# SPI_peripherals.net
KiCad netlist of a schematic drawn in Altium Designer
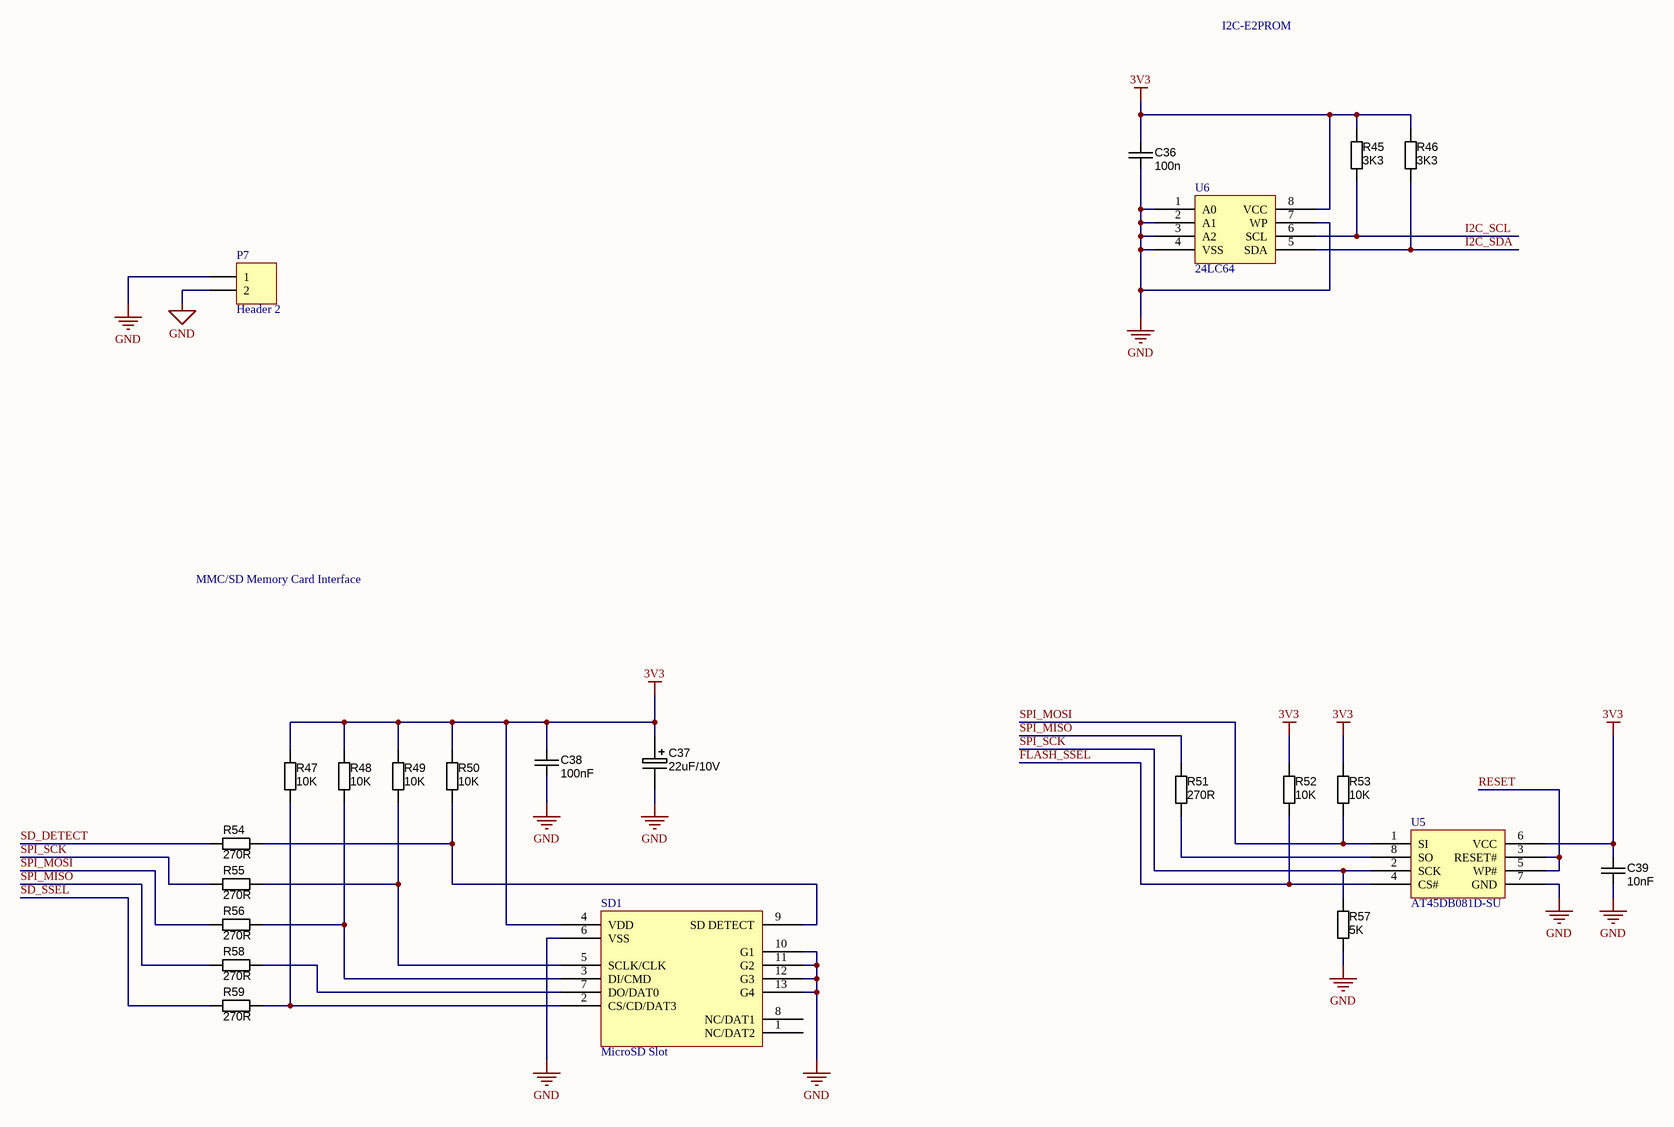
[diagram p0: SPI peripherals.SchDoc]

(export (version "E")
  (design (tool "Eeschema 10.0.6"))
  (components
    (comp (ref "C36")
      (value "100n")
      (footprint "CAPC1608N")
      (description "Capacitor SMD Cer 100nF 10% 50V X7R 0805")
      (fields (field (name "TOLERANCE") "?0%") (field (name "Comment") "approved sub OK"))
      (libsource (lib "PBL - Capacitors") (part "CAPC_100n_0805"))
    )
    (comp (ref "C37")
      (value "~")
      (footprint "CAPC3216N")
      (description "Capacitor SMD Tantalum 1uF 20% 10V 0805")
      (fields (field (name "TOLERANCE") "?0%") (field (name "RATINGS") "22uF/10V"))
      (libsource (lib "PBL - Capacitors") (part "CAPT_1u_0805_10V"))
    )
    (comp (ref "C38")
      (value "100nF")
      (footprint "CAPC1608N")
      (description "Capacitor SMD Cer 100nF 10% 50V X7R 0805")
      (fields (field (name "TOLERANCE") "?0%") (field (name "Comment") "approved sub OK"))
      (libsource (lib "PBL - Capacitors") (part "CAPC_100n_0805"))
    )
    (comp (ref "C39")
      (value "10nF")
      (footprint "CAPC1608N")
      (description "Capacitor SMD Cer 100nF 10% 50V X7R 0805")
      (fields (field (name "TOLERANCE") "?0%") (field (name "Comment") "approved sub OK"))
      (libsource (lib "PBL - Capacitors") (part "CAPC_100n_0805"))
    )
    (comp (ref "P7")
      (value "Header 2")
      (footprint "HDR1X2")
      (description "Header, 2-Pin")
      (fields (field (name "PUBLISHER") "Altium Limited"))
      (libsource (lib "Miscellaneous Connectors") (part "Header 2"))
    )
    (comp (ref "R45")
      (value "3K3")
      (footprint "RESC1005N")
      (description "Resistor SMD chip 330 Ohm 0.063W 5% 0402")
      (fields (field (name "TOLERANCE") "?%") (field (name "Comment") "Thick Film"))
      (libsource (lib "PBL - Resistors") (part "RES_330R_0402_5%"))
    )
    (comp (ref "R46")
      (value "3K3")
      (footprint "RESC1005N")
      (description "Resistor SMD chip 330 Ohm 0.063W 5% 0402")
      (fields (field (name "TOLERANCE") "?%") (field (name "Comment") "Thick Film"))
      (libsource (lib "PBL - Resistors") (part "RES_330R_0402_5%"))
    )
    (comp (ref "R47")
      (value "10K")
      (footprint "RESC1005N")
      (description "Resistor SMD chip 330 Ohm 0.063W 5% 0402")
      (fields (field (name "TOLERANCE") "?%") (field (name "Comment") "Thick Film"))
      (libsource (lib "") (part "RES_330R_0402_5%_2"))
    )
    (comp (ref "R48")
      (value "10K")
      (footprint "RESC1005N")
      (description "Resistor SMD chip 330 Ohm 0.063W 5% 0402")
      (fields (field (name "TOLERANCE") "?%") (field (name "Comment") "Thick Film"))
      (libsource (lib "") (part "RES_330R_0402_5%_2"))
    )
    (comp (ref "R49")
      (value "10K")
      (footprint "RESC1005N")
      (description "Resistor SMD chip 330 Ohm 0.063W 5% 0402")
      (fields (field (name "TOLERANCE") "?%") (field (name "Comment") "Thick Film"))
      (libsource (lib "") (part "RES_330R_0402_5%_2"))
    )
    (comp (ref "R50")
      (value "10K")
      (footprint "RESC1005N")
      (description "Resistor SMD chip 330 Ohm 0.063W 5% 0402")
      (fields (field (name "TOLERANCE") "?%") (field (name "Comment") "Thick Film"))
      (libsource (lib "") (part "RES_330R_0402_5%_2"))
    )
    (comp (ref "R51")
      (value "270R")
      (footprint "RESC1005N")
      (description "Resistor SMD chip 330 Ohm 0.063W 5% 0402")
      (fields (field (name "TOLERANCE") "?%") (field (name "Comment") "Thick Film"))
      (libsource (lib "PBL - Resistors") (part "RES_330R_0402_5%"))
    )
    (comp (ref "R52")
      (value "10K")
      (footprint "RESC1005N")
      (description "Resistor SMD chip 330 Ohm 0.063W 5% 0402")
      (fields (field (name "TOLERANCE") "?%") (field (name "Comment") "Thick Film"))
      (libsource (lib "PBL - Resistors") (part "RES_330R_0402_5%"))
    )
    (comp (ref "R53")
      (value "10K")
      (footprint "RESC1005N")
      (description "Resistor SMD chip 330 Ohm 0.063W 5% 0402")
      (fields (field (name "TOLERANCE") "?%") (field (name "Comment") "Thick Film"))
      (libsource (lib "PBL - Resistors") (part "RES_330R_0402_5%"))
    )
    (comp (ref "R54")
      (value "270R")
      (footprint "RESC1005N")
      (description "Resistor SMD chip 330 Ohm 0.063W 5% 0402")
      (fields (field (name "TOLERANCE") "?%") (field (name "Comment") "Thick Film"))
      (libsource (lib "") (part "RES_330R_0402_5%_1"))
    )
    (comp (ref "R55")
      (value "270R")
      (footprint "RESC1005N")
      (description "Resistor SMD chip 330 Ohm 0.063W 5% 0402")
      (fields (field (name "TOLERANCE") "?%") (field (name "Comment") "Thick Film"))
      (libsource (lib "") (part "RES_330R_0402_5%_1"))
    )
    (comp (ref "R56")
      (value "270R")
      (footprint "RESC1005N")
      (description "Resistor SMD chip 330 Ohm 0.063W 5% 0402")
      (fields (field (name "TOLERANCE") "?%") (field (name "Comment") "Thick Film"))
      (libsource (lib "") (part "RES_330R_0402_5%_1"))
    )
    (comp (ref "R57")
      (value "5K")
      (footprint "RESC1005N")
      (description "Resistor SMD chip 330 Ohm 0.063W 5% 0402")
      (fields (field (name "TOLERANCE") "?%") (field (name "Comment") "Thick Film"))
      (libsource (lib "PBL - Resistors") (part "RES_330R_0402_5%"))
    )
    (comp (ref "R58")
      (value "270R")
      (footprint "RESC1005N")
      (description "Resistor SMD chip 330 Ohm 0.063W 5% 0402")
      (fields (field (name "TOLERANCE") "?%") (field (name "Comment") "Thick Film"))
      (libsource (lib "") (part "RES_330R_0402_5%_1"))
    )
    (comp (ref "R59")
      (value "270R")
      (footprint "RESC1005N")
      (description "Resistor SMD chip 330 Ohm 0.063W 5% 0402")
      (fields (field (name "TOLERANCE") "?%") (field (name "Comment") "Thick Film"))
      (libsource (lib "") (part "RES_330R_0402_5%_1"))
    )
    (comp (ref "SD1")
      (value "MicroSD Slot")
      (footprint "MICROSD Slot")
      (libsource (lib "AltiumLib1") (part "MicroSD Slot"))
    )
    (comp (ref "U5")
      (value "AT45DB081D-SU")
      (footprint "SOIJ-SM8_N")
      (libsource (lib "Schlib1") (part "AT45DB081D-SU"))
    )
    (comp (ref "U6") (value "24LC64") (footprint "SOIJ-SM8_N") (libsource (lib "Schlib1") (part "24LC64")))
  )
  (nets
    (net (code "1") (name "/FLASH_SSEL") (class "Default")
      (node (ref "R52") (pin "2") (pinfunction "2_2") (pintype "passive"))
      (node (ref "U5") (pin "4") (pinfunction "CS#_4") (pintype "passive"))
    )
    (net (code "2") (name "/I2C_SCL") (class "Default")
      (node (ref "R45") (pin "2") (pinfunction "2_2") (pintype "passive"))
      (node (ref "U6") (pin "6") (pinfunction "SCL_6") (pintype "passive"))
    )
    (net (code "3") (name "/I2C_SDA") (class "Default")
      (node (ref "R46") (pin "2") (pinfunction "2_2") (pintype "passive"))
      (node (ref "U6") (pin "5") (pinfunction "SDA_5") (pintype "passive"))
    )
    (net (code "4") (name "/RESET") (class "Default")
      (node (ref "U5") (pin "3") (pinfunction "RESET#_3") (pintype "passive"))
      (node (ref "U5") (pin "5") (pinfunction "WP#_5") (pintype "passive"))
    )
    (net (code "5") (name "/SD_DETECT") (class "Default")
      (node (ref "R54") (pin "2") (pinfunction "2_2") (pintype "passive"))
    )
    (net (code "6") (name "/SD_SSEL") (class "Default")
      (node (ref "R59") (pin "2") (pinfunction "2_2") (pintype "passive"))
    )
    (net (code "7") (name "/SPI_MISO") (class "Default")
      (node (ref "R51") (pin "1") (pinfunction "1_1") (pintype "passive"))
      (node (ref "R58") (pin "2") (pinfunction "2_2") (pintype "passive"))
    )
    (net (code "8") (name "/SPI_MOSI") (class "Default")
      (node (ref "R53") (pin "2") (pinfunction "2_2") (pintype "passive"))
      (node (ref "R56") (pin "2") (pinfunction "2_2") (pintype "passive"))
      (node (ref "U5") (pin "1") (pinfunction "SI_1") (pintype "passive"))
    )
    (net (code "9") (name "/SPI_SCK") (class "Default")
      (node (ref "R55") (pin "2") (pinfunction "2_2") (pintype "passive"))
      (node (ref "R57") (pin "1") (pinfunction "1_1") (pintype "passive"))
      (node (ref "U5") (pin "2") (pinfunction "SCK_2") (pintype "passive"))
    )
    (net (code "10") (name "3V3") (class "Default")
      (node (ref "C36") (pin "1") (pintype "passive"))
      (node (ref "C37") (pin "1") (pintype "passive"))
      (node (ref "C38") (pin "1") (pintype "passive"))
      (node (ref "C39") (pin "2") (pintype "passive"))
      (node (ref "R45") (pin "1") (pinfunction "1_1") (pintype "passive"))
      (node (ref "R46") (pin "1") (pinfunction "1_1") (pintype "passive"))
      (node (ref "R47") (pin "2") (pinfunction "2_2") (pintype "passive"))
      (node (ref "R48") (pin "2") (pinfunction "2_2") (pintype "passive"))
      (node (ref "R49") (pin "2") (pinfunction "2_2") (pintype "passive"))
      (node (ref "R50") (pin "2") (pinfunction "2_2") (pintype "passive"))
      (node (ref "R52") (pin "1") (pinfunction "1_1") (pintype "passive"))
      (node (ref "R53") (pin "1") (pinfunction "1_1") (pintype "passive"))
      (node (ref "SD1") (pin "4") (pinfunction "VDD_4") (pintype "passive"))
      (node (ref "U5") (pin "6") (pinfunction "VCC_6") (pintype "passive"))
      (node (ref "U6") (pin "8") (pinfunction "VCC_8") (pintype "passive"))
    )
    (net (code "11") (name "GND") (class "Default")
      (node (ref "C36") (pin "2") (pintype "passive"))
      (node (ref "C37") (pin "2") (pintype "passive"))
      (node (ref "C38") (pin "2") (pintype "passive"))
      (node (ref "C39") (pin "1") (pintype "passive"))
      (node (ref "P7") (pin "1") (pinfunction "1_1") (pintype "passive"))
      (node (ref "P7") (pin "2") (pinfunction "2_2") (pintype "passive"))
      (node (ref "R57") (pin "2") (pinfunction "2_2") (pintype "passive"))
      (node (ref "SD1") (pin "10") (pinfunction "G1_10") (pintype "passive"))
      (node (ref "SD1") (pin "11") (pinfunction "G2_11") (pintype "passive"))
      (node (ref "SD1") (pin "12") (pinfunction "G3_12") (pintype "passive"))
      (node (ref "SD1") (pin "13") (pinfunction "G4_13") (pintype "passive"))
      (node (ref "SD1") (pin "6") (pinfunction "VSS_6") (pintype "passive"))
      (node (ref "U5") (pin "7") (pinfunction "GND_7") (pintype "passive"))
      (node (ref "U6") (pin "1") (pinfunction "A0_1") (pintype "passive"))
      (node (ref "U6") (pin "2") (pinfunction "A1_2") (pintype "passive"))
      (node (ref "U6") (pin "3") (pinfunction "A2_3") (pintype "passive"))
      (node (ref "U6") (pin "4") (pinfunction "VSS_4") (pintype "passive"))
      (node (ref "U6") (pin "7") (pinfunction "WP_7") (pintype "passive"))
    )
    (net (code "12") (name "Net-(SD1-CS{slash}CD{slash}DAT3)") (class "Default")
      (node (ref "R47") (pin "1") (pinfunction "1_1") (pintype "passive"))
      (node (ref "R59") (pin "1") (pinfunction "1_1") (pintype "passive"))
      (node (ref "SD1") (pin "2") (pinfunction "CS/CD/DAT3_2") (pintype "passive"))
    )
    (net (code "13") (name "Net-(SD1-DI{slash}CMD)") (class "Default")
      (node (ref "R48") (pin "1") (pinfunction "1_1") (pintype "passive"))
      (node (ref "R56") (pin "1") (pinfunction "1_1") (pintype "passive"))
      (node (ref "SD1") (pin "3") (pinfunction "DI/CMD_3") (pintype "passive"))
    )
    (net (code "14") (name "Net-(SD1-DO{slash}DAT0)") (class "Default")
      (node (ref "R58") (pin "1") (pinfunction "1_1") (pintype "passive"))
      (node (ref "SD1") (pin "7") (pinfunction "DO/DAT0_7") (pintype "passive"))
    )
    (net (code "15") (name "Net-(SD1-SCLK{slash}CLK)") (class "Default")
      (node (ref "R49") (pin "1") (pinfunction "1_1") (pintype "passive"))
      (node (ref "R55") (pin "1") (pinfunction "1_1") (pintype "passive"))
      (node (ref "SD1") (pin "5") (pinfunction "SCLK/CLK_5") (pintype "passive"))
    )
    (net (code "16") (name "Net-(SD1-SD_DETECT)") (class "Default")
      (node (ref "R50") (pin "1") (pinfunction "1_1") (pintype "passive"))
      (node (ref "R54") (pin "1") (pinfunction "1_1") (pintype "passive"))
      (node (ref "SD1") (pin "9") (pinfunction "SD_DETECT_9") (pintype "passive"))
    )
    (net (code "17") (name "Net-(U5-SO)") (class "Default")
      (node (ref "R51") (pin "2") (pinfunction "2_2") (pintype "passive"))
      (node (ref "U5") (pin "8") (pinfunction "SO_8") (pintype "passive"))
    )
    (net (code "18") (name "unconnected-(SD1-NC{slash}DAT1-Pad8)") (class "Default")
      (node (ref "SD1") (pin "8") (pinfunction "NC/DAT1_8") (pintype "passive"))
    )
    (net (code "19") (name "unconnected-(SD1-NC{slash}DAT2-Pad1)") (class "Default")
      (node (ref "SD1") (pin "1") (pinfunction "NC/DAT2_1") (pintype "passive"))
    )
  )
)
